# fpga.net
KiCad netlist of a schematic drawn in Altium Designer
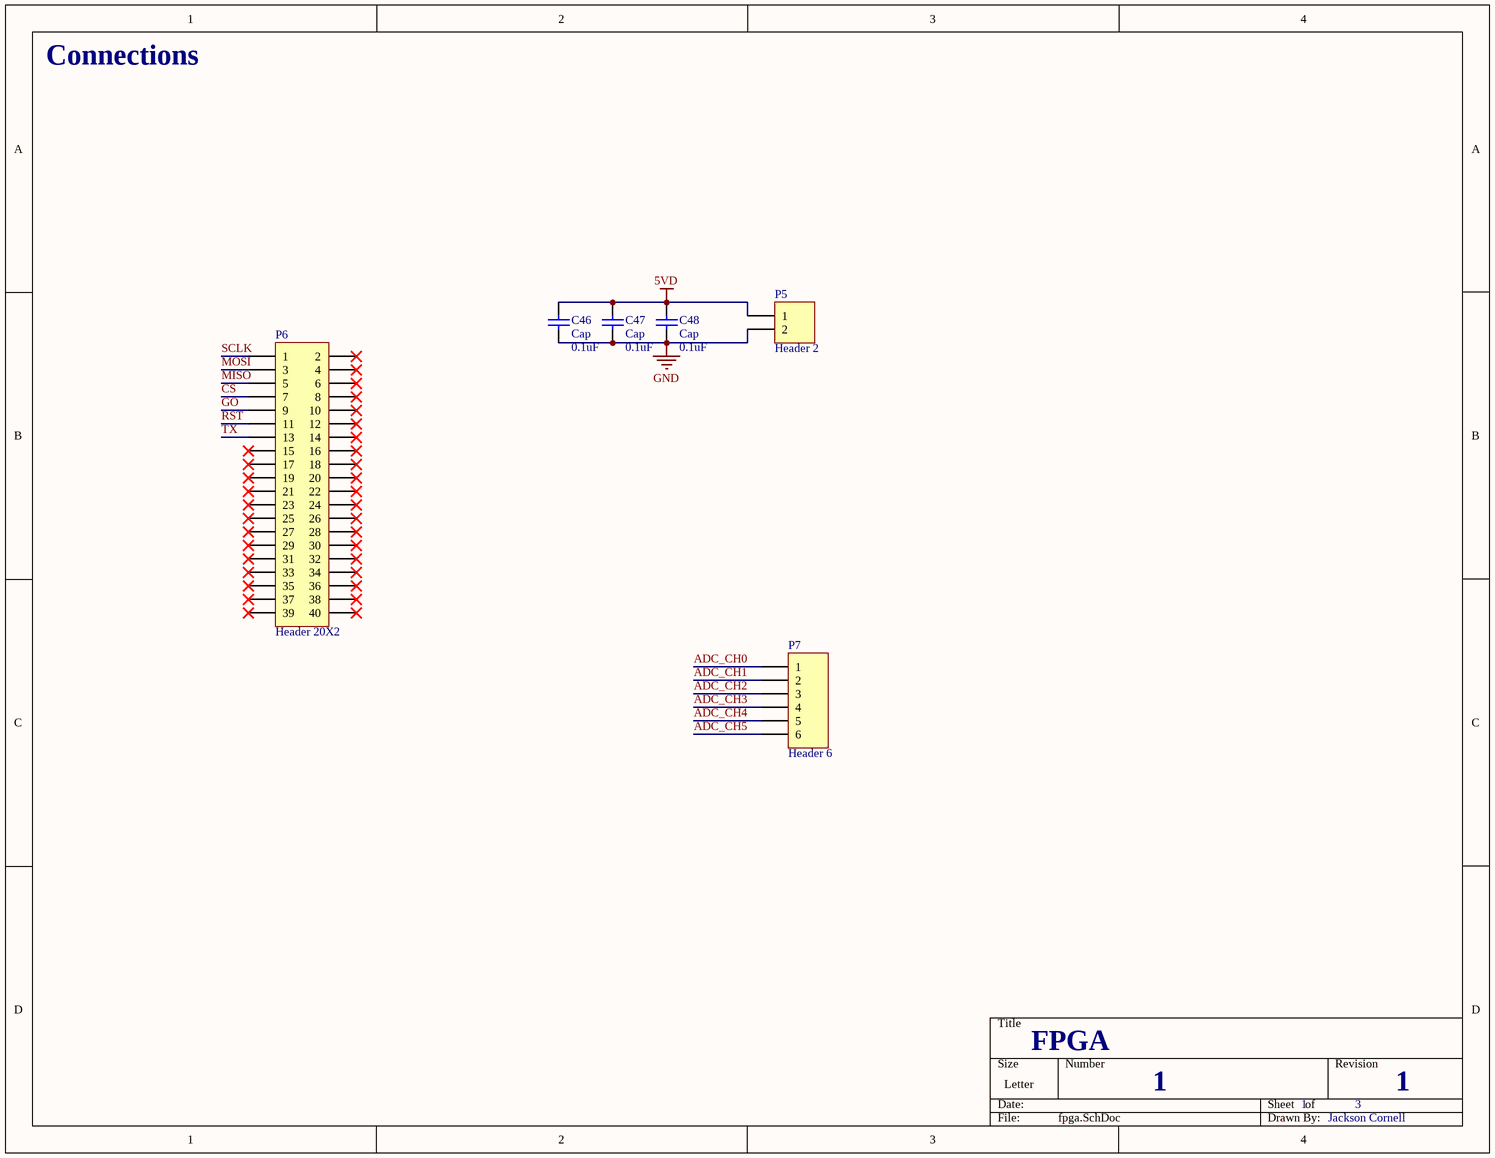
[diagram p0: fpga.SchDoc]

(export (version "E")
  (design (tool "Eeschema 10.0.6"))
  (components
    (comp (ref "C46")
      (value "Cap")
      (footprint "CAPC0805")
      (description "Capacitor")
      (fields (field (name "ALTIUM_VALUE") "0.1uF") (field (name "PUBLISHER") "Altium Limited"))
      (libsource (lib "Miscellaneous Devices") (part "Cap"))
    )
    (comp (ref "C47")
      (value "Cap")
      (footprint "CAPC0805")
      (description "Capacitor")
      (fields (field (name "ALTIUM_VALUE") "0.1uF") (field (name "PUBLISHER") "Altium Limited"))
      (libsource (lib "Miscellaneous Devices") (part "Cap"))
    )
    (comp (ref "C48")
      (value "Cap")
      (footprint "CAPC0805")
      (description "Capacitor")
      (fields (field (name "ALTIUM_VALUE") "0.1uF") (field (name "PUBLISHER") "Altium Limited"))
      (libsource (lib "Miscellaneous Devices") (part "Cap"))
    )
    (comp (ref "P5")
      (value "Header 2")
      (footprint "HDR1X2")
      (description "Header, 2-Pin")
      (fields (field (name "PUBLISHER") "Altium Limited"))
      (libsource (lib "Miscellaneous Connectors") (part "Header 2"))
    )
    (comp (ref "P6")
      (value "Header 20X2")
      (footprint "HDR2X20")
      (description "Header, 20-Pin, Dual row")
      (fields (field (name "PUBLISHER") "Altium Limited"))
      (libsource (lib "Miscellaneous Connectors") (part "Header 20X2"))
    )
    (comp (ref "P7")
      (value "Header 6")
      (footprint "HDR1X6")
      (description "Header, 6-Pin")
      (fields (field (name "PUBLISHER") "Altium Limited"))
      (libsource (lib "Miscellaneous Connectors") (part "Header 6"))
    )
  )
  (nets
    (net (code "1") (name "/ADC_CH0") (class "Default")
      (node (ref "P7") (pin "1") (pinfunction "1_1") (pintype "passive"))
    )
    (net (code "2") (name "/ADC_CH1") (class "Default")
      (node (ref "P7") (pin "2") (pinfunction "2_2") (pintype "passive"))
    )
    (net (code "3") (name "/ADC_CH2") (class "Default")
      (node (ref "P7") (pin "3") (pinfunction "3_3") (pintype "passive"))
    )
    (net (code "4") (name "/ADC_CH3") (class "Default")
      (node (ref "P7") (pin "4") (pinfunction "4_4") (pintype "passive"))
    )
    (net (code "5") (name "/ADC_CH4") (class "Default")
      (node (ref "P7") (pin "5") (pinfunction "5_5") (pintype "passive"))
    )
    (net (code "6") (name "/ADC_CH5") (class "Default")
      (node (ref "P7") (pin "6") (pinfunction "6_6") (pintype "passive"))
    )
    (net (code "7") (name "/CS") (class "Default")
      (node (ref "P6") (pin "7") (pinfunction "7_7") (pintype "passive"))
    )
    (net (code "8") (name "/GO") (class "Default")
      (node (ref "P6") (pin "9") (pinfunction "9_9") (pintype "passive"))
    )
    (net (code "9") (name "/MISO") (class "Default")
      (node (ref "P6") (pin "5") (pinfunction "5_5") (pintype "passive"))
    )
    (net (code "10") (name "/MOSI") (class "Default")
      (node (ref "P6") (pin "3") (pinfunction "3_3") (pintype "passive"))
    )
    (net (code "11") (name "/RST") (class "Default")
      (node (ref "P6") (pin "11") (pinfunction "11_11") (pintype "passive"))
    )
    (net (code "12") (name "/SCLK") (class "Default")
      (node (ref "P6") (pin "1") (pinfunction "1_1") (pintype "passive"))
    )
    (net (code "13") (name "/TX") (class "Default")
      (node (ref "P6") (pin "13") (pinfunction "13_13") (pintype "passive"))
    )
    (net (code "14") (name "5VD") (class "Default")
      (node (ref "C46") (pin "2") (pinfunction "2_2") (pintype "passive"))
      (node (ref "C47") (pin "2") (pinfunction "2_2") (pintype "passive"))
      (node (ref "C48") (pin "2") (pinfunction "2_2") (pintype "passive"))
      (node (ref "P5") (pin "1") (pinfunction "1_1") (pintype "passive"))
    )
    (net (code "15") (name "GND") (class "Default")
      (node (ref "C46") (pin "1") (pinfunction "1_1") (pintype "passive"))
      (node (ref "C47") (pin "1") (pinfunction "1_1") (pintype "passive"))
      (node (ref "C48") (pin "1") (pinfunction "1_1") (pintype "passive"))
      (node (ref "P5") (pin "2") (pinfunction "2_2") (pintype "passive"))
    )
    (net (code "16") (name "unconnected-(P6-Pad2)") (class "Default")
      (node (ref "P6") (pin "2") (pinfunction "2_2") (pintype "passive+no_connect"))
    )
    (net (code "17") (name "unconnected-(P6-Pad4)") (class "Default")
      (node (ref "P6") (pin "4") (pinfunction "4_4") (pintype "passive+no_connect"))
    )
    (net (code "18") (name "unconnected-(P6-Pad6)") (class "Default")
      (node (ref "P6") (pin "6") (pinfunction "6_6") (pintype "passive+no_connect"))
    )
    (net (code "19") (name "unconnected-(P6-Pad8)") (class "Default")
      (node (ref "P6") (pin "8") (pinfunction "8_8") (pintype "passive+no_connect"))
    )
    (net (code "20") (name "unconnected-(P6-Pad10)") (class "Default")
      (node (ref "P6") (pin "10") (pinfunction "10_10") (pintype "passive+no_connect"))
    )
    (net (code "21") (name "unconnected-(P6-Pad12)") (class "Default")
      (node (ref "P6") (pin "12") (pinfunction "12_12") (pintype "passive+no_connect"))
    )
    (net (code "22") (name "unconnected-(P6-Pad14)") (class "Default")
      (node (ref "P6") (pin "14") (pinfunction "14_14") (pintype "passive+no_connect"))
    )
    (net (code "23") (name "unconnected-(P6-Pad15)") (class "Default")
      (node (ref "P6") (pin "15") (pinfunction "15_15") (pintype "passive+no_connect"))
    )
    (net (code "24") (name "unconnected-(P6-Pad16)") (class "Default")
      (node (ref "P6") (pin "16") (pinfunction "16_16") (pintype "passive+no_connect"))
    )
    (net (code "25") (name "unconnected-(P6-Pad17)") (class "Default")
      (node (ref "P6") (pin "17") (pinfunction "17_17") (pintype "passive+no_connect"))
    )
    (net (code "26") (name "unconnected-(P6-Pad18)") (class "Default")
      (node (ref "P6") (pin "18") (pinfunction "18_18") (pintype "passive+no_connect"))
    )
    (net (code "27") (name "unconnected-(P6-Pad19)") (class "Default")
      (node (ref "P6") (pin "19") (pinfunction "19_19") (pintype "passive+no_connect"))
    )
    (net (code "28") (name "unconnected-(P6-Pad20)") (class "Default")
      (node (ref "P6") (pin "20") (pinfunction "20_20") (pintype "passive+no_connect"))
    )
    (net (code "29") (name "unconnected-(P6-Pad21)") (class "Default")
      (node (ref "P6") (pin "21") (pinfunction "21_21") (pintype "passive+no_connect"))
    )
    (net (code "30") (name "unconnected-(P6-Pad22)") (class "Default")
      (node (ref "P6") (pin "22") (pinfunction "22_22") (pintype "passive+no_connect"))
    )
    (net (code "31") (name "unconnected-(P6-Pad23)") (class "Default")
      (node (ref "P6") (pin "23") (pinfunction "23_23") (pintype "passive+no_connect"))
    )
    (net (code "32") (name "unconnected-(P6-Pad24)") (class "Default")
      (node (ref "P6") (pin "24") (pinfunction "24_24") (pintype "passive+no_connect"))
    )
    (net (code "33") (name "unconnected-(P6-Pad25)") (class "Default")
      (node (ref "P6") (pin "25") (pinfunction "25_25") (pintype "passive+no_connect"))
    )
    (net (code "34") (name "unconnected-(P6-Pad26)") (class "Default")
      (node (ref "P6") (pin "26") (pinfunction "26_26") (pintype "passive+no_connect"))
    )
    (net (code "35") (name "unconnected-(P6-Pad27)") (class "Default")
      (node (ref "P6") (pin "27") (pinfunction "27_27") (pintype "passive+no_connect"))
    )
    (net (code "36") (name "unconnected-(P6-Pad28)") (class "Default")
      (node (ref "P6") (pin "28") (pinfunction "28_28") (pintype "passive+no_connect"))
    )
    (net (code "37") (name "unconnected-(P6-Pad29)") (class "Default")
      (node (ref "P6") (pin "29") (pinfunction "29_29") (pintype "passive+no_connect"))
    )
    (net (code "38") (name "unconnected-(P6-Pad30)") (class "Default")
      (node (ref "P6") (pin "30") (pinfunction "30_30") (pintype "passive+no_connect"))
    )
    (net (code "39") (name "unconnected-(P6-Pad31)") (class "Default")
      (node (ref "P6") (pin "31") (pinfunction "31_31") (pintype "passive+no_connect"))
    )
    (net (code "40") (name "unconnected-(P6-Pad32)") (class "Default")
      (node (ref "P6") (pin "32") (pinfunction "32_32") (pintype "passive+no_connect"))
    )
    (net (code "41") (name "unconnected-(P6-Pad33)") (class "Default")
      (node (ref "P6") (pin "33") (pinfunction "33_33") (pintype "passive+no_connect"))
    )
    (net (code "42") (name "unconnected-(P6-Pad34)") (class "Default")
      (node (ref "P6") (pin "34") (pinfunction "34_34") (pintype "passive+no_connect"))
    )
    (net (code "43") (name "unconnected-(P6-Pad35)") (class "Default")
      (node (ref "P6") (pin "35") (pinfunction "35_35") (pintype "passive+no_connect"))
    )
    (net (code "44") (name "unconnected-(P6-Pad36)") (class "Default")
      (node (ref "P6") (pin "36") (pinfunction "36_36") (pintype "passive+no_connect"))
    )
    (net (code "45") (name "unconnected-(P6-Pad37)") (class "Default")
      (node (ref "P6") (pin "37") (pinfunction "37_37") (pintype "passive+no_connect"))
    )
    (net (code "46") (name "unconnected-(P6-Pad38)") (class "Default")
      (node (ref "P6") (pin "38") (pinfunction "38_38") (pintype "passive+no_connect"))
    )
    (net (code "47") (name "unconnected-(P6-Pad39)") (class "Default")
      (node (ref "P6") (pin "39") (pinfunction "39_39") (pintype "passive+no_connect"))
    )
    (net (code "48") (name "unconnected-(P6-Pad40)") (class "Default")
      (node (ref "P6") (pin "40") (pinfunction "40_40") (pintype "passive+no_connect"))
    )
  )
)
